# besc_io_pm_sch.net
KiCad netlist of a schematic drawn in Altium Designer
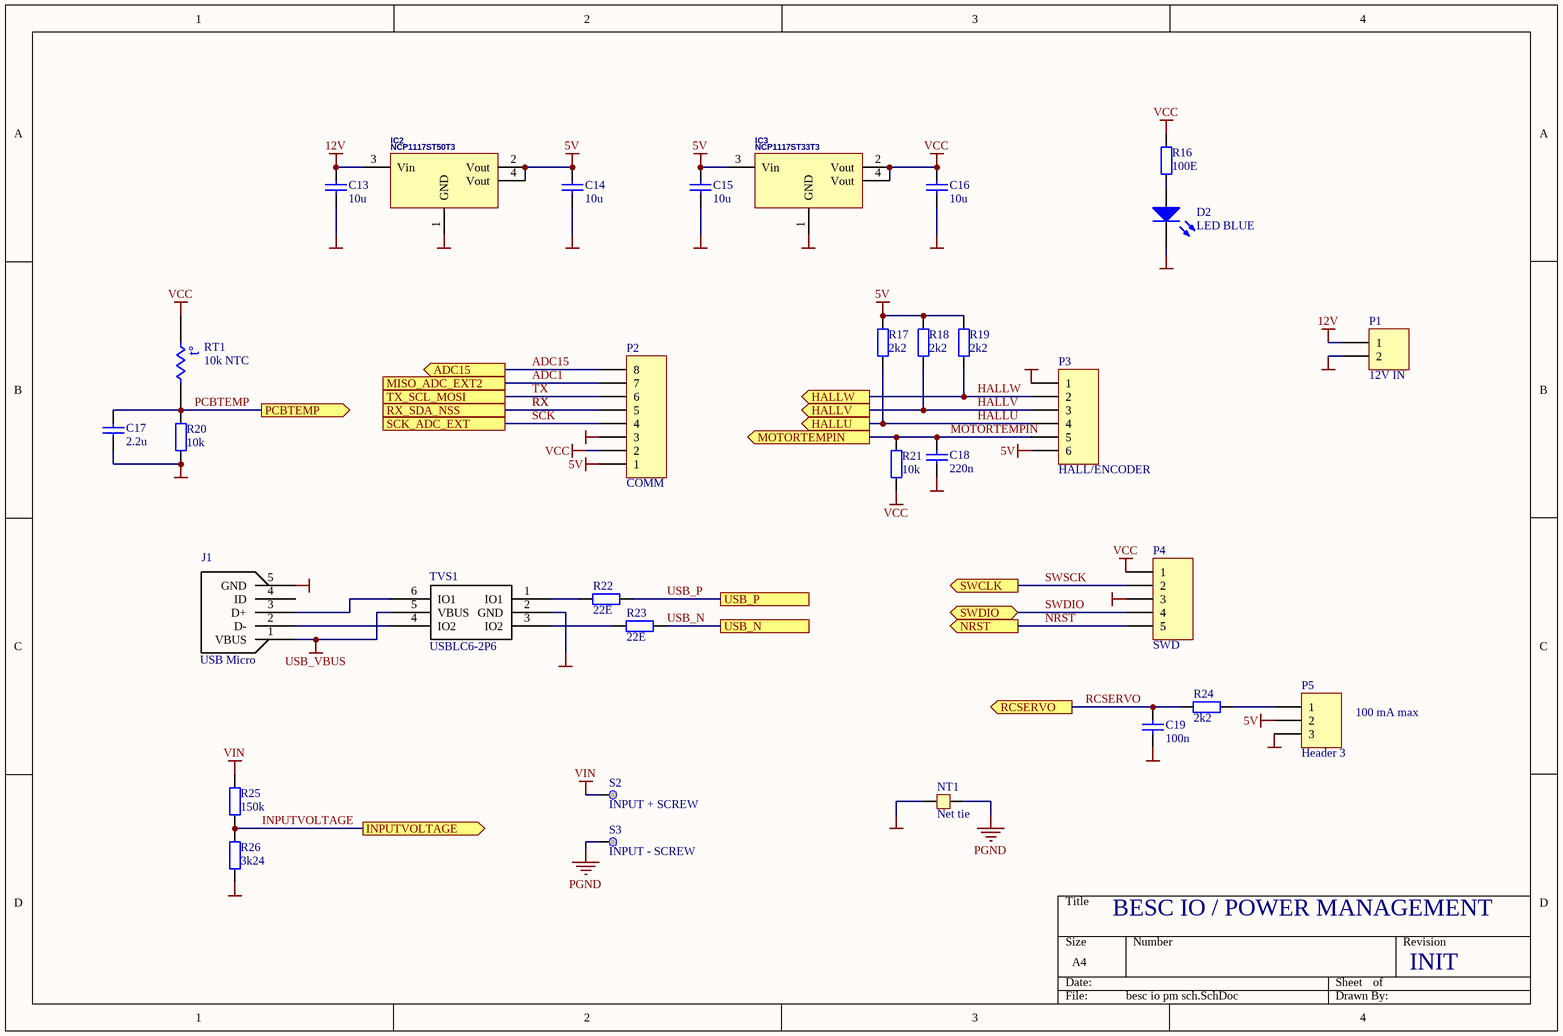
[diagram p0: besc io pm sch.SchDoc]

(export (version "E")
  (design (tool "Eeschema 10.0.6"))
  (components
    (comp (ref "C13")
      (value "10u")
      (footprint "0805")
      (description "Capacitor")
      (fields (field (name "PUBLISHER") "Altium Limited"))
      (libsource (lib "Miscellaneous Devices") (part "Cap"))
    )
    (comp (ref "C14")
      (value "10u")
      (footprint "0805")
      (description "Capacitor")
      (fields (field (name "PUBLISHER") "Altium Limited"))
      (libsource (lib "Miscellaneous Devices") (part "Cap"))
    )
    (comp (ref "C15")
      (value "10u")
      (footprint "0805")
      (description "Capacitor")
      (fields (field (name "PUBLISHER") "Altium Limited"))
      (libsource (lib "Miscellaneous Devices") (part "Cap"))
    )
    (comp (ref "C16")
      (value "10u")
      (footprint "0805")
      (description "Capacitor")
      (fields (field (name "PUBLISHER") "Altium Limited"))
      (libsource (lib "Miscellaneous Devices") (part "Cap"))
    )
    (comp (ref "C17")
      (value "2.2u")
      (footprint "0603")
      (description "Capacitor")
      (fields (field (name "PUBLISHER") "Altium Limited"))
      (libsource (lib "Miscellaneous Devices") (part "Cap"))
    )
    (comp (ref "C18")
      (value "220n")
      (footprint "0603")
      (description "Capacitor")
      (fields (field (name "PUBLISHER") "Altium Limited"))
      (libsource (lib "Miscellaneous Devices") (part "Cap"))
    )
    (comp (ref "C19")
      (value "100n")
      (footprint "0603")
      (description "Capacitor")
      (fields (field (name "PUBLISHER") "Altium Limited"))
      (libsource (lib "Miscellaneous Devices") (part "Cap"))
    )
    (comp (ref "D2")
      (value "LED BLUE")
      (footprint "0805-diode")
      (description "Typical INFRARED GaAs LED")
      (fields (field (name "PUBLISHER") "Altium Limited"))
      (libsource (lib "Miscellaneous Devices") (part "LED0"))
    )
    (comp (ref "IC2")
      (value "NCP1117ST50T3")
      (footprint "SOT223_M")
      (libsource (lib "*") (part "VOLTREG_LD1117S33"))
    )
    (comp (ref "IC3")
      (value "NCP1117ST33T3")
      (footprint "SOT223_M")
      (libsource (lib "*") (part "VOLTREG_LD1117S33"))
    )
    (comp (ref "J1")
      (value "USB Micro")
      (footprint "MOLEX - 47346-0001 - MICRO USB TYPE B, RECEPTACLE, BOTTOM")
      (description "SOCKET, USB MINI-AB THRU HOLE")
      (fields (field (name "MANUFACTURER") "MOLEX") (field (name "PART NUMBER") "565790511"))
      (libsource (lib "moja") (part "USB Mini AB"))
    )
    (comp (ref "NT1") (value "Net tie") (footprint "NETTIE12mil") (libsource (lib "moja") (part "Net tie")))
    (comp (ref "P1")
      (value "12V IN")
      (footprint "JST SM02B-PASS-TB")
      (description "JST SM02B-PASS-TB")
      (fields (field (name "PUBLISHER") "Altium Limited"))
      (libsource (lib "Miscellaneous Connectors") (part "Header 2"))
    )
    (comp (ref "P2")
      (value "COMM")
      (footprint "JST SM08B-PASS-TB")
      (description "JST SM08B-PASS-TB")
      (fields (field (name "PUBLISHER") "Altium Limited"))
      (libsource (lib "Miscellaneous Connectors") (part "Header 8"))
    )
    (comp (ref "P3")
      (value "HALL/ENCODER")
      (footprint "JST SM06B-PASS-TB")
      (description "JST SM06B-PASS-TB")
      (fields (field (name "PUBLISHER") "Altium Limited"))
      (libsource (lib "Miscellaneous Connectors") (part "Header 6"))
    )
    (comp (ref "P4")
      (value "SWD")
      (footprint "Header 1x5 male")
      (description "Header, 5-Pin")
      (fields (field (name "PUBLISHER") "Altium Limited"))
      (libsource (lib "Miscellaneous Connectors") (part "Header 5"))
    )
    (comp (ref "P5")
      (value "Header 3")
      (footprint "JST SM03B-PASS-TB")
      (description "Header, 3-Pin")
      (fields (field (name "PUBLISHER") "Altium Limited"))
      (libsource (lib "Miscellaneous Connectors") (part "Header 3"))
    )
    (comp (ref "R16")
      (value "100E")
      (footprint "0603")
      (description "Resistor")
      (fields (field (name "PUBLISHER") "Altium Limited"))
      (libsource (lib "Miscellaneous Devices") (part "Res2"))
    )
    (comp (ref "R17")
      (value "2k2")
      (footprint "0603")
      (description "Resistor")
      (fields (field (name "PUBLISHER") "Altium Limited"))
      (libsource (lib "Miscellaneous Devices") (part "Res2"))
    )
    (comp (ref "R18")
      (value "2k2")
      (footprint "0603")
      (description "Resistor")
      (fields (field (name "PUBLISHER") "Altium Limited"))
      (libsource (lib "Miscellaneous Devices") (part "Res2"))
    )
    (comp (ref "R19")
      (value "2k2")
      (footprint "0603")
      (description "Resistor")
      (fields (field (name "PUBLISHER") "Altium Limited"))
      (libsource (lib "Miscellaneous Devices") (part "Res2"))
    )
    (comp (ref "R20")
      (value "10k")
      (footprint "0603")
      (description "Resistor")
      (fields (field (name "PUBLISHER") "Altium Limited"))
      (libsource (lib "Miscellaneous Devices") (part "Res2"))
    )
    (comp (ref "R21")
      (value "10k")
      (footprint "0603")
      (description "Resistor")
      (fields (field (name "PUBLISHER") "Altium Limited"))
      (libsource (lib "") (part "Res2_1"))
    )
    (comp (ref "R22")
      (value "22E")
      (footprint "0603")
      (description "Resistor")
      (fields (field (name "PUBLISHER") "Altium Limited"))
      (libsource (lib "") (part "Res2_3"))
    )
    (comp (ref "R23")
      (value "22E")
      (footprint "0603")
      (description "Resistor")
      (fields (field (name "PUBLISHER") "Altium Limited"))
      (libsource (lib "") (part "Res2_3"))
    )
    (comp (ref "R24")
      (value "2k2")
      (footprint "0603")
      (description "Resistor")
      (fields (field (name "PUBLISHER") "Altium Limited"))
      (libsource (lib "") (part "Res2_2"))
    )
    (comp (ref "R25")
      (value "150k")
      (footprint "0603")
      (description "Resistor")
      (fields (field (name "PUBLISHER") "Altium Limited"))
      (libsource (lib "Miscellaneous Devices") (part "Res2"))
    )
    (comp (ref "R26")
      (value "3k24")
      (footprint "0603")
      (description "Resistor")
      (fields (field (name "PUBLISHER") "Altium Limited"))
      (libsource (lib "Miscellaneous Devices") (part "Res2"))
    )
    (comp (ref "RT1")
      (value "10k NTC")
      (footprint "0603")
      (description "Thermistor")
      (fields (field (name "PUBLISHER") "Altium Limited"))
      (libsource (lib "Miscellaneous Devices") (part "Res Thermal"))
    )
    (comp (ref "S2")
      (value "INPUT + SCREW")
      (footprint "WP-SHFU-M6")
      (description "7461098")
      (libsource (lib "moja") (part "En_pin"))
    )
    (comp (ref "S3")
      (value "INPUT - SCREW")
      (footprint "WP-SHFU-M6")
      (description "7461098")
      (libsource (lib "moja") (part "En_pin"))
    )
    (comp (ref "TVS1")
      (value "USBLC6-2P6")
      (footprint "SOT23127P600-8N")
      (libsource (lib "moja") (part "USBLC6-2P6"))
    )
  )
  (nets
    (net (code "1") (name "/ADC1") (class "Default")
      (node (ref "P2") (pin "7") (pinfunction "7_7") (pintype "passive"))
    )
    (net (code "2") (name "/ADC15") (class "Default")
      (node (ref "P2") (pin "8") (pinfunction "8_8") (pintype "passive"))
    )
    (net (code "3") (name "/HALLU") (class "Default")
      (node (ref "P3") (pin "4") (pinfunction "4_4") (pintype "passive"))
      (node (ref "R17") (pin "2") (pinfunction "2_2") (pintype "passive"))
    )
    (net (code "4") (name "/HALLV") (class "Default")
      (node (ref "P3") (pin "3") (pinfunction "3_3") (pintype "passive"))
      (node (ref "R18") (pin "2") (pinfunction "2_2") (pintype "passive"))
    )
    (net (code "5") (name "/HALLW") (class "Default")
      (node (ref "P3") (pin "2") (pinfunction "2_2") (pintype "passive"))
      (node (ref "R19") (pin "2") (pinfunction "2_2") (pintype "passive"))
    )
    (net (code "6") (name "/INPUTVOLTAGE") (class "Default")
      (node (ref "R25") (pin "2") (pinfunction "2_2") (pintype "passive"))
      (node (ref "R26") (pin "1") (pinfunction "1_1") (pintype "passive"))
    )
    (net (code "7") (name "/MOTORTEMPIN") (class "Default")
      (node (ref "C18") (pin "1") (pinfunction "1_1") (pintype "passive"))
      (node (ref "P3") (pin "5") (pinfunction "5_5") (pintype "passive"))
      (node (ref "R21") (pin "2") (pinfunction "2_2") (pintype "passive"))
    )
    (net (code "8") (name "/NRST") (class "Default")
      (node (ref "P4") (pin "5") (pinfunction "5_5") (pintype "passive"))
    )
    (net (code "9") (name "/PCBTEMP") (class "Default")
      (node (ref "C17") (pin "1") (pinfunction "1_1") (pintype "passive"))
      (node (ref "R20") (pin "1") (pinfunction "1_1") (pintype "passive"))
      (node (ref "RT1") (pin "2") (pinfunction "2_2") (pintype "passive"))
    )
    (net (code "10") (name "/RCSERVO") (class "Default")
      (node (ref "C19") (pin "2") (pinfunction "2_2") (pintype "passive"))
      (node (ref "R24") (pin "1") (pinfunction "1_1") (pintype "passive"))
    )
    (net (code "11") (name "/RX") (class "Default")
      (node (ref "P2") (pin "5") (pinfunction "5_5") (pintype "passive"))
    )
    (net (code "12") (name "/SCK") (class "Default")
      (node (ref "P2") (pin "4") (pinfunction "4_4") (pintype "passive"))
    )
    (net (code "13") (name "/SWDIO") (class "Default")
      (node (ref "P4") (pin "4") (pinfunction "4_4") (pintype "passive"))
    )
    (net (code "14") (name "/SWSCK") (class "Default")
      (node (ref "P4") (pin "2") (pinfunction "2_2") (pintype "passive"))
    )
    (net (code "15") (name "/TX") (class "Default")
      (node (ref "P2") (pin "6") (pinfunction "6_6") (pintype "passive"))
    )
    (net (code "16") (name "/USB_N") (class "Default")
      (node (ref "R23") (pin "1") (pinfunction "1_1") (pintype "passive"))
    )
    (net (code "17") (name "/USB_P") (class "Default")
      (node (ref "R22") (pin "1") (pinfunction "1_1") (pintype "passive"))
    )
    (net (code "18") (name "5V") (class "Default")
      (node (ref "C14") (pin "1") (pinfunction "1_1") (pintype "passive"))
      (node (ref "C15") (pin "1") (pinfunction "1_1") (pintype "passive"))
      (node (ref "IC2") (pin "2") (pinfunction "Vout_2") (pintype "passive"))
      (node (ref "IC2") (pin "4") (pinfunction "Vout_4") (pintype "passive"))
      (node (ref "IC3") (pin "3") (pinfunction "Vin_3") (pintype "passive"))
      (node (ref "P2") (pin "1") (pinfunction "1_1") (pintype "passive"))
      (node (ref "P3") (pin "6") (pinfunction "6_6") (pintype "passive"))
      (node (ref "P5") (pin "2") (pinfunction "2_2") (pintype "passive"))
      (node (ref "R17") (pin "1") (pinfunction "1_1") (pintype "passive"))
      (node (ref "R18") (pin "1") (pinfunction "1_1") (pintype "passive"))
      (node (ref "R19") (pin "1") (pinfunction "1_1") (pintype "passive"))
    )
    (net (code "19") (name "12V") (class "Default")
      (node (ref "C13") (pin "1") (pinfunction "1_1") (pintype "passive"))
      (node (ref "IC2") (pin "3") (pinfunction "Vin_3") (pintype "passive"))
      (node (ref "P1") (pin "1") (pinfunction "1_1") (pintype "passive"))
    )
    (net (code "20") (name "LGND") (class "Default")
      (node (ref "C13") (pin "2") (pinfunction "2_2") (pintype "passive"))
      (node (ref "C14") (pin "2") (pinfunction "2_2") (pintype "passive"))
      (node (ref "C15") (pin "2") (pinfunction "2_2") (pintype "passive"))
      (node (ref "C16") (pin "2") (pinfunction "2_2") (pintype "passive"))
      (node (ref "C17") (pin "2") (pinfunction "2_2") (pintype "passive"))
      (node (ref "C18") (pin "2") (pinfunction "2_2") (pintype "passive"))
      (node (ref "C19") (pin "1") (pinfunction "1_1") (pintype "passive"))
      (node (ref "D2") (pin "2") (pinfunction "K_2") (pintype "passive"))
      (node (ref "IC2") (pin "1") (pinfunction "GND_1") (pintype "passive"))
      (node (ref "IC3") (pin "1") (pinfunction "GND_1") (pintype "passive"))
      (node (ref "J1") (pin "5") (pinfunction "GND_5") (pintype "power_in"))
      (node (ref "NT1") (pin "1") (pintype "passive"))
      (node (ref "P1") (pin "2") (pinfunction "2_2") (pintype "passive"))
      (node (ref "P2") (pin "3") (pinfunction "3_3") (pintype "passive"))
      (node (ref "P3") (pin "1") (pinfunction "1_1") (pintype "passive"))
      (node (ref "P4") (pin "3") (pinfunction "3_3") (pintype "passive"))
      (node (ref "P5") (pin "3") (pinfunction "3_3") (pintype "passive"))
      (node (ref "R20") (pin "2") (pinfunction "2_2") (pintype "passive"))
      (node (ref "R26") (pin "2") (pinfunction "2_2") (pintype "passive"))
      (node (ref "TVS1") (pin "2") (pinfunction "GND_2") (pintype "passive"))
    )
    (net (code "21") (name "Net-(D2-A)") (class "Default")
      (node (ref "D2") (pin "1") (pinfunction "A_1") (pintype "passive"))
      (node (ref "R16") (pin "2") (pinfunction "2_2") (pintype "passive"))
    )
    (net (code "22") (name "Net-(J1-D+)") (class "Default")
      (node (ref "J1") (pin "3") (pinfunction "D+_3") (pintype "power_in"))
      (node (ref "TVS1") (pin "6") (pinfunction "IO1_6") (pintype "passive"))
    )
    (net (code "23") (name "Net-(J1-D-)") (class "Default")
      (node (ref "J1") (pin "2") (pinfunction "D-_2") (pintype "power_in"))
      (node (ref "TVS1") (pin "4") (pinfunction "IO2_4") (pintype "passive"))
    )
    (net (code "24") (name "Net-(P5-Pad1)") (class "Default")
      (node (ref "P5") (pin "1") (pinfunction "1_1") (pintype "passive"))
      (node (ref "R24") (pin "2") (pinfunction "2_2") (pintype "passive"))
    )
    (net (code "25") (name "Net-(R22-Pad2)") (class "Default")
      (node (ref "R22") (pin "2") (pinfunction "2_2") (pintype "passive"))
      (node (ref "TVS1") (pin "1") (pinfunction "IO1_1") (pintype "passive"))
    )
    (net (code "26") (name "Net-(R23-Pad2)") (class "Default")
      (node (ref "R23") (pin "2") (pinfunction "2_2") (pintype "passive"))
      (node (ref "TVS1") (pin "3") (pinfunction "IO2_3") (pintype "passive"))
    )
    (net (code "27") (name "PGND") (class "Default")
      (node (ref "NT1") (pin "2") (pintype "passive"))
      (node (ref "S3") (pin "1") (pinfunction "1_1") (pintype "passive"))
    )
    (net (code "28") (name "USB_VBUS") (class "Default")
      (node (ref "J1") (pin "1") (pinfunction "VBUS_1") (pintype "power_in"))
      (node (ref "TVS1") (pin "5") (pinfunction "VBUS_5") (pintype "passive"))
    )
    (net (code "29") (name "VCC") (class "Default")
      (node (ref "C16") (pin "1") (pinfunction "1_1") (pintype "passive"))
      (node (ref "IC3") (pin "2") (pinfunction "Vout_2") (pintype "passive"))
      (node (ref "IC3") (pin "4") (pinfunction "Vout_4") (pintype "passive"))
      (node (ref "P2") (pin "2") (pinfunction "2_2") (pintype "passive"))
      (node (ref "P4") (pin "1") (pinfunction "1_1") (pintype "passive"))
      (node (ref "R16") (pin "1") (pinfunction "1_1") (pintype "passive"))
      (node (ref "R21") (pin "1") (pinfunction "1_1") (pintype "passive"))
      (node (ref "RT1") (pin "1") (pinfunction "1_1") (pintype "passive"))
    )
    (net (code "30") (name "VIN") (class "Default")
      (node (ref "R25") (pin "1") (pinfunction "1_1") (pintype "passive"))
      (node (ref "S2") (pin "1") (pinfunction "1_1") (pintype "passive"))
    )
    (net (code "31") (name "unconnected-(J1-ID-Pad4)") (class "Default")
      (node (ref "J1") (pin "4") (pinfunction "ID_4") (pintype "power_in"))
    )
  )
)
